# ece411_t2_schematic.net
KiCad netlist of a schematic drawn in EAGLE
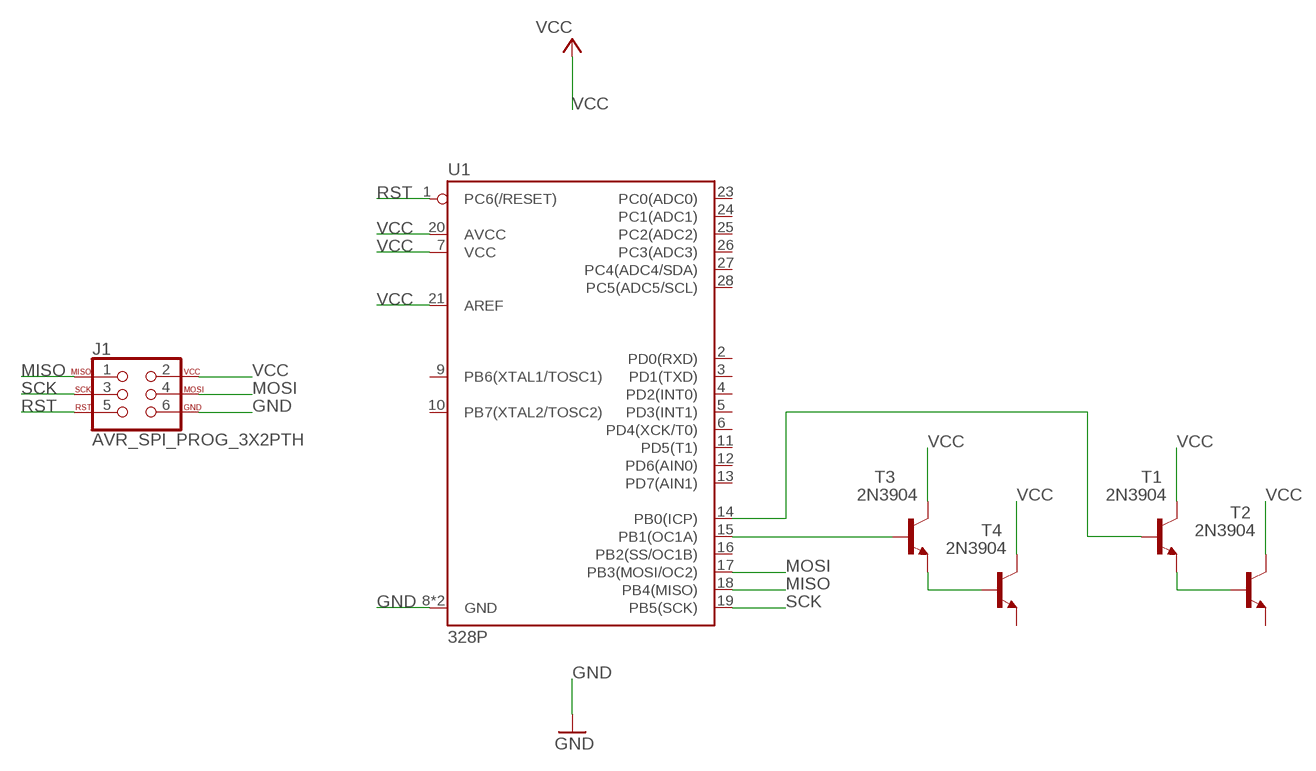
[diagram p0: schematic, sheet 1]

(export (version "E")
  (design (tool "Eeschema 10.0.6"))
  (components
    (comp (ref "J1")
      (value "AVR_SPI_PROG_3X2PTH")
      (footprint "eagle-import:2X3")
      (libsource (lib "eagle-import") (part "AVR_SPI_PROG_3X2PTH"))
    )
    (comp (ref "T1")
      (value "2N3904")
      (footprint "eagle-import:TO92")
      (libsource (lib "eagle-import") (part "2N3904"))
    )
    (comp (ref "T2")
      (value "2N3904")
      (footprint "eagle-import:TO92")
      (libsource (lib "eagle-import") (part "2N3904"))
    )
    (comp (ref "T3")
      (value "2N3904")
      (footprint "eagle-import:TO92")
      (libsource (lib "eagle-import") (part "2N3904"))
    )
    (comp (ref "T4")
      (value "2N3904")
      (footprint "eagle-import:TO92")
      (libsource (lib "eagle-import") (part "2N3904"))
    )
    (comp (ref "U1")
      (value "328P")
      (footprint "eagle-import:DIP28")
      (libsource (lib "eagle-import") (part "ATMEGA328P_PDIP"))
    )
  )
  (nets
    (net (code "1") (name "/MISO") (class "Default")
      (node (ref "J1") (pin "1") (pinfunction "1_1") (pintype "passive"))
      (node (ref "U1") (pin "18") (pinfunction "PB4(MISO)_18") (pintype "bidirectional"))
    )
    (net (code "2") (name "/MOSI") (class "Default")
      (node (ref "J1") (pin "4") (pinfunction "4_4") (pintype "passive"))
      (node (ref "U1") (pin "17") (pinfunction "PB3(MOSI/OC2)_17") (pintype "bidirectional"))
    )
    (net (code "3") (name "/RST") (class "Default")
      (node (ref "J1") (pin "5") (pinfunction "5_5") (pintype "passive"))
      (node (ref "U1") (pin "1") (pinfunction "PC6(/RESET)_1") (pintype "bidirectional"))
    )
    (net (code "4") (name "/SCK") (class "Default")
      (node (ref "J1") (pin "3") (pinfunction "3_3") (pintype "passive"))
      (node (ref "U1") (pin "19") (pinfunction "PB5(SCK)_19") (pintype "bidirectional"))
    )
    (net (code "5") (name "GND") (class "Default")
      (node (ref "J1") (pin "6") (pinfunction "6_6") (pintype "passive"))
      (node (ref "U1") (pin "22") (pinfunction "GND_22") (pintype "bidirectional"))
      (node (ref "U1") (pin "8") (pinfunction "GND_8") (pintype "bidirectional"))
    )
    (net (code "6") (name "Net-(T1-B)") (class "Default")
      (node (ref "T1") (pin "2") (pinfunction "B_2") (pintype "passive"))
      (node (ref "U1") (pin "14") (pinfunction "PB0(ICP)_14") (pintype "bidirectional"))
    )
    (net (code "7") (name "Net-(T1-E)") (class "Default")
      (node (ref "T1") (pin "3") (pinfunction "E_3") (pintype "passive"))
      (node (ref "T2") (pin "2") (pinfunction "B_2") (pintype "passive"))
    )
    (net (code "8") (name "Net-(T3-B)") (class "Default")
      (node (ref "T3") (pin "2") (pinfunction "B_2") (pintype "passive"))
      (node (ref "U1") (pin "15") (pinfunction "PB1(OC1A)_15") (pintype "bidirectional"))
    )
    (net (code "9") (name "Net-(T3-E)") (class "Default")
      (node (ref "T3") (pin "3") (pinfunction "E_3") (pintype "passive"))
      (node (ref "T4") (pin "2") (pinfunction "B_2") (pintype "passive"))
    )
    (net (code "10") (name "VCC") (class "Default")
      (node (ref "J1") (pin "2") (pinfunction "2_2") (pintype "passive"))
      (node (ref "T1") (pin "1") (pinfunction "C_1") (pintype "passive"))
      (node (ref "T2") (pin "1") (pinfunction "C_1") (pintype "passive"))
      (node (ref "T3") (pin "1") (pinfunction "C_1") (pintype "passive"))
      (node (ref "T4") (pin "1") (pinfunction "C_1") (pintype "passive"))
      (node (ref "U1") (pin "20") (pinfunction "AVCC_20") (pintype "bidirectional"))
      (node (ref "U1") (pin "21") (pinfunction "AREF_21") (pintype "bidirectional"))
      (node (ref "U1") (pin "7") (pinfunction "VCC_7") (pintype "bidirectional"))
    )
    (net (code "11") (name "unconnected-(T2-E-Pad3)") (class "Default")
      (node (ref "T2") (pin "3") (pinfunction "E_3") (pintype "passive"))
    )
    (net (code "12") (name "unconnected-(T4-E-Pad3)") (class "Default")
      (node (ref "T4") (pin "3") (pinfunction "E_3") (pintype "passive"))
    )
    (net (code "13") (name "unconnected-(U1-PB2(SS{slash}OC1B)-Pad16)") (class "Default")
      (node (ref "U1") (pin "16") (pinfunction "PB2(SS/OC1B)_16") (pintype "bidirectional"))
    )
    (net (code "14") (name "unconnected-(U1-PB6(XTAL1{slash}TOSC1)-Pad9)") (class "Default")
      (node (ref "U1") (pin "9") (pinfunction "PB6(XTAL1/TOSC1)_9") (pintype "bidirectional"))
    )
    (net (code "15") (name "unconnected-(U1-PB7(XTAL2{slash}TOSC2)-Pad10)") (class "Default")
      (node (ref "U1") (pin "10") (pinfunction "PB7(XTAL2/TOSC2)_10") (pintype "bidirectional"))
    )
    (net (code "16") (name "unconnected-(U1-PC0(ADC0)-Pad23)") (class "Default")
      (node (ref "U1") (pin "23") (pinfunction "PC0(ADC0)_23") (pintype "bidirectional"))
    )
    (net (code "17") (name "unconnected-(U1-PC1(ADC1)-Pad24)") (class "Default")
      (node (ref "U1") (pin "24") (pinfunction "PC1(ADC1)_24") (pintype "bidirectional"))
    )
    (net (code "18") (name "unconnected-(U1-PC2(ADC2)-Pad25)") (class "Default")
      (node (ref "U1") (pin "25") (pinfunction "PC2(ADC2)_25") (pintype "bidirectional"))
    )
    (net (code "19") (name "unconnected-(U1-PC3(ADC3)-Pad26)") (class "Default")
      (node (ref "U1") (pin "26") (pinfunction "PC3(ADC3)_26") (pintype "bidirectional"))
    )
    (net (code "20") (name "unconnected-(U1-PC4(ADC4{slash}SDA)-Pad27)") (class "Default")
      (node (ref "U1") (pin "27") (pinfunction "PC4(ADC4/SDA)_27") (pintype "bidirectional"))
    )
    (net (code "21") (name "unconnected-(U1-PC5(ADC5{slash}SCL)-Pad28)") (class "Default")
      (node (ref "U1") (pin "28") (pinfunction "PC5(ADC5/SCL)_28") (pintype "bidirectional"))
    )
    (net (code "22") (name "unconnected-(U1-PD0(RXD)-Pad2)") (class "Default")
      (node (ref "U1") (pin "2") (pinfunction "PD0(RXD)_2") (pintype "bidirectional"))
    )
    (net (code "23") (name "unconnected-(U1-PD1(TXD)-Pad3)") (class "Default")
      (node (ref "U1") (pin "3") (pinfunction "PD1(TXD)_3") (pintype "bidirectional"))
    )
    (net (code "24") (name "unconnected-(U1-PD2(INT0)-Pad4)") (class "Default")
      (node (ref "U1") (pin "4") (pinfunction "PD2(INT0)_4") (pintype "bidirectional"))
    )
    (net (code "25") (name "unconnected-(U1-PD3(INT1)-Pad5)") (class "Default")
      (node (ref "U1") (pin "5") (pinfunction "PD3(INT1)_5") (pintype "bidirectional"))
    )
    (net (code "26") (name "unconnected-(U1-PD4(XCK{slash}T0)-Pad6)") (class "Default")
      (node (ref "U1") (pin "6") (pinfunction "PD4(XCK/T0)_6") (pintype "bidirectional"))
    )
    (net (code "27") (name "unconnected-(U1-PD5(T1)-Pad11)") (class "Default")
      (node (ref "U1") (pin "11") (pinfunction "PD5(T1)_11") (pintype "bidirectional"))
    )
    (net (code "28") (name "unconnected-(U1-PD6(AIN0)-Pad12)") (class "Default")
      (node (ref "U1") (pin "12") (pinfunction "PD6(AIN0)_12") (pintype "bidirectional"))
    )
    (net (code "29") (name "unconnected-(U1-PD7(AIN1)-Pad13)") (class "Default")
      (node (ref "U1") (pin "13") (pinfunction "PD7(AIN1)_13") (pintype "bidirectional"))
    )
  )
)
